# esp-01-rc-plane.net
KiCad netlist of a schematic drawn in EAGLE
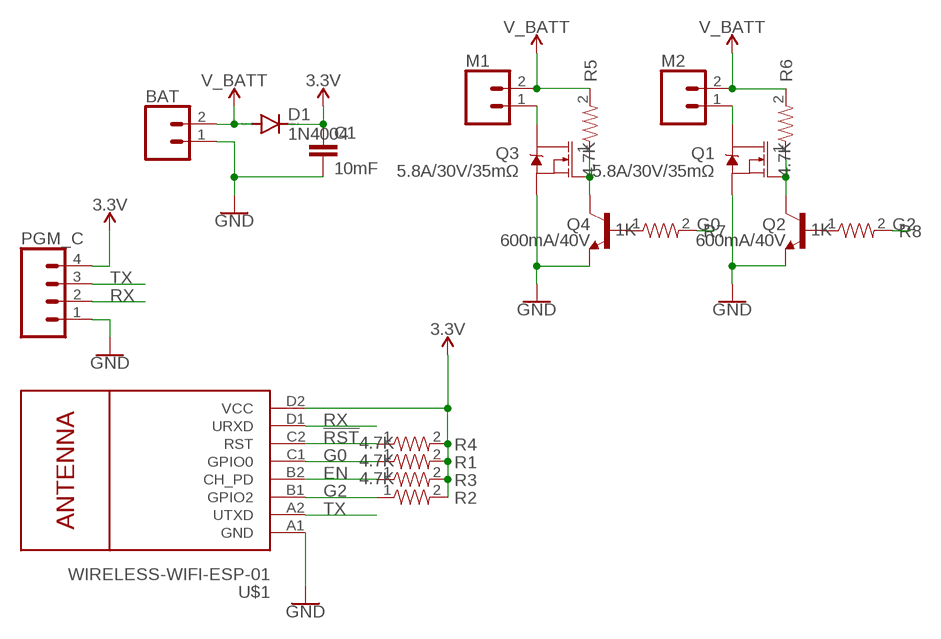
[diagram p0: schematic, sheet 1]

(export (version "E")
  (design (tool "Eeschema 10.0.6"))
  (components
    (comp (ref "BAT")
      (value "CONN_02")
      (footprint "eagle-import:1X02")
      (libsource (lib "eagle-import") (part "CONN_02"))
    )
    (comp (ref "C1")
      (value "10mF")
      (footprint "eagle-import:0805")
      (libsource (lib "eagle-import") (part "CAP-805"))
    )
    (comp (ref "D1")
      (value "1N4004")
      (footprint "eagle-import:DO41-10")
      (libsource (lib "eagle-import") (part "1N4004"))
    )
    (comp (ref "M1")
      (value "CONN_02")
      (footprint "eagle-import:1X02")
      (libsource (lib "eagle-import") (part "CONN_02"))
    )
    (comp (ref "M2")
      (value "CONN_02")
      (footprint "eagle-import:1X02")
      (libsource (lib "eagle-import") (part "CONN_02"))
    )
    (comp (ref "PGM_C")
      (value "CONN_04")
      (footprint "eagle-import:1X04")
      (libsource (lib "eagle-import") (part "CONN_04"))
    )
    (comp (ref "Q1")
      (value "5.8A/30V/35mΩ")
      (footprint "eagle-import:SOT23-3")
      (libsource (lib "eagle-import") (part "MOSFET-NCH-AO3404A"))
    )
    (comp (ref "Q2")
      (value "600mA/40V")
      (footprint "eagle-import:SOT23-3")
      (libsource (lib "eagle-import") (part "TRANS_NPN-MMBT2222AL"))
    )
    (comp (ref "Q3")
      (value "5.8A/30V/35mΩ")
      (footprint "eagle-import:SOT23-3")
      (libsource (lib "eagle-import") (part "MOSFET-NCH-AO3404A"))
    )
    (comp (ref "Q4")
      (value "600mA/40V")
      (footprint "eagle-import:SOT23-3")
      (libsource (lib "eagle-import") (part "TRANS_NPN-MMBT2222AL"))
    )
    (comp (ref "R1")
      (value "4.7K")
      (footprint "eagle-import:0805")
      (libsource (lib "eagle-import") (part "RESISTOR-805"))
    )
    (comp (ref "R2")
      (value "4.7K")
      (footprint "eagle-import:0805")
      (libsource (lib "eagle-import") (part "RESISTOR-805"))
    )
    (comp (ref "R3")
      (value "4.7K")
      (footprint "eagle-import:0805")
      (libsource (lib "eagle-import") (part "RESISTOR-805"))
    )
    (comp (ref "R4")
      (value "4.7K")
      (footprint "eagle-import:0805")
      (libsource (lib "eagle-import") (part "RESISTOR-805"))
    )
    (comp (ref "R5")
      (value "4.7K")
      (footprint "eagle-import:0805")
      (libsource (lib "eagle-import") (part "RESISTOR-805"))
    )
    (comp (ref "R6")
      (value "4.7K")
      (footprint "eagle-import:0805")
      (libsource (lib "eagle-import") (part "RESISTOR-805"))
    )
    (comp (ref "R7")
      (value "1K")
      (footprint "eagle-import:0805")
      (libsource (lib "eagle-import") (part "RESISTOR-805"))
    )
    (comp (ref "R8")
      (value "1K")
      (footprint "eagle-import:0805")
      (libsource (lib "eagle-import") (part "RESISTOR-805"))
    )
    (comp (ref "U$1")
      (value "WIRELESS-WIFI-ESP-01")
      (footprint "eagle-import:WIRELESS-WIFI-ESP-01")
      (libsource (lib "eagle-import") (part "WIRELESS-WIFI-ESP-01"))
    )
  )
  (nets
    (net (code "1") (name "/EN") (class "Default")
      (node (ref "R3") (pin "1") (pinfunction "1_1") (pintype "passive"))
      (node (ref "U$1") (pin "B2") (pinfunction "CH_PD_B2") (pintype "bidirectional"))
    )
    (net (code "2") (name "/G0") (class "Default")
      (node (ref "R1") (pin "1") (pinfunction "1_1") (pintype "passive"))
      (node (ref "R7") (pin "2") (pinfunction "2_2") (pintype "passive"))
      (node (ref "U$1") (pin "C1") (pinfunction "GPIO0_C1") (pintype "bidirectional"))
    )
    (net (code "3") (name "/G2") (class "Default")
      (node (ref "R2") (pin "1") (pinfunction "1_1") (pintype "passive"))
      (node (ref "R8") (pin "2") (pinfunction "2_2") (pintype "passive"))
      (node (ref "U$1") (pin "B1") (pinfunction "GPIO2_B1") (pintype "bidirectional"))
    )
    (net (code "4") (name "/RX") (class "Default")
      (node (ref "PGM_C") (pin "2") (pinfunction "2_2") (pintype "passive"))
      (node (ref "U$1") (pin "D1") (pinfunction "URXD_D1") (pintype "bidirectional"))
    )
    (net (code "5") (name "/TX") (class "Default")
      (node (ref "PGM_C") (pin "3") (pinfunction "3_3") (pintype "passive"))
      (node (ref "U$1") (pin "A2") (pinfunction "UTXD_A2") (pintype "bidirectional"))
    )
    (net (code "6") (name "/~{RST}") (class "Default")
      (node (ref "R4") (pin "1") (pinfunction "1_1") (pintype "passive"))
      (node (ref "U$1") (pin "C2") (pinfunction "RST_C2") (pintype "bidirectional"))
    )
    (net (code "7") (name "3.3V") (class "Default")
      (node (ref "C1") (pin "1") (pinfunction "1_1") (pintype "passive"))
      (node (ref "D1") (pin "C") (pinfunction "C_C") (pintype "passive"))
      (node (ref "PGM_C") (pin "4") (pinfunction "4_4") (pintype "passive"))
      (node (ref "R1") (pin "2") (pinfunction "2_2") (pintype "passive"))
      (node (ref "R2") (pin "2") (pinfunction "2_2") (pintype "passive"))
      (node (ref "R3") (pin "2") (pinfunction "2_2") (pintype "passive"))
      (node (ref "R4") (pin "2") (pinfunction "2_2") (pintype "passive"))
      (node (ref "U$1") (pin "D2") (pinfunction "VCC_D2") (pintype "power_in"))
    )
    (net (code "8") (name "GND") (class "Default")
      (node (ref "BAT") (pin "1") (pinfunction "1_1") (pintype "passive"))
      (node (ref "C1") (pin "2") (pinfunction "2_2") (pintype "passive"))
      (node (ref "PGM_C") (pin "1") (pinfunction "1_1") (pintype "passive"))
      (node (ref "Q1") (pin "2") (pinfunction "S_2") (pintype "bidirectional"))
      (node (ref "Q2") (pin "2") (pinfunction "E_2") (pintype "passive"))
      (node (ref "Q3") (pin "2") (pinfunction "S_2") (pintype "bidirectional"))
      (node (ref "Q4") (pin "2") (pinfunction "E_2") (pintype "passive"))
      (node (ref "U$1") (pin "A1") (pinfunction "GND_A1") (pintype "power_in"))
    )
    (net (code "9") (name "Net-(Q1-D)") (class "Default")
      (node (ref "M2") (pin "1") (pinfunction "1_1") (pintype "passive"))
      (node (ref "Q1") (pin "3") (pinfunction "D_3") (pintype "bidirectional"))
    )
    (net (code "10") (name "Net-(Q1-G)") (class "Default")
      (node (ref "Q1") (pin "1") (pinfunction "G_1") (pintype "bidirectional"))
      (node (ref "Q2") (pin "3") (pinfunction "C_3") (pintype "passive"))
      (node (ref "R6") (pin "1") (pinfunction "1_1") (pintype "passive"))
    )
    (net (code "11") (name "Net-(Q2-B)") (class "Default")
      (node (ref "Q2") (pin "1") (pinfunction "B_1") (pintype "passive"))
      (node (ref "R8") (pin "1") (pinfunction "1_1") (pintype "passive"))
    )
    (net (code "12") (name "Net-(Q3-D)") (class "Default")
      (node (ref "M1") (pin "1") (pinfunction "1_1") (pintype "passive"))
      (node (ref "Q3") (pin "3") (pinfunction "D_3") (pintype "bidirectional"))
    )
    (net (code "13") (name "Net-(Q3-G)") (class "Default")
      (node (ref "Q3") (pin "1") (pinfunction "G_1") (pintype "bidirectional"))
      (node (ref "Q4") (pin "3") (pinfunction "C_3") (pintype "passive"))
      (node (ref "R5") (pin "1") (pinfunction "1_1") (pintype "passive"))
    )
    (net (code "14") (name "Net-(Q4-B)") (class "Default")
      (node (ref "Q4") (pin "1") (pinfunction "B_1") (pintype "passive"))
      (node (ref "R7") (pin "1") (pinfunction "1_1") (pintype "passive"))
    )
    (net (code "15") (name "V_BATT") (class "Default")
      (node (ref "BAT") (pin "2") (pinfunction "2_2") (pintype "passive"))
      (node (ref "D1") (pin "A") (pinfunction "A_A") (pintype "passive"))
      (node (ref "M1") (pin "2") (pinfunction "2_2") (pintype "passive"))
      (node (ref "M2") (pin "2") (pinfunction "2_2") (pintype "passive"))
      (node (ref "R5") (pin "2") (pinfunction "2_2") (pintype "passive"))
      (node (ref "R6") (pin "2") (pinfunction "2_2") (pintype "passive"))
    )
  )
)
